# sheet4.net
KiCad netlist of a schematic drawn in Altium Designer
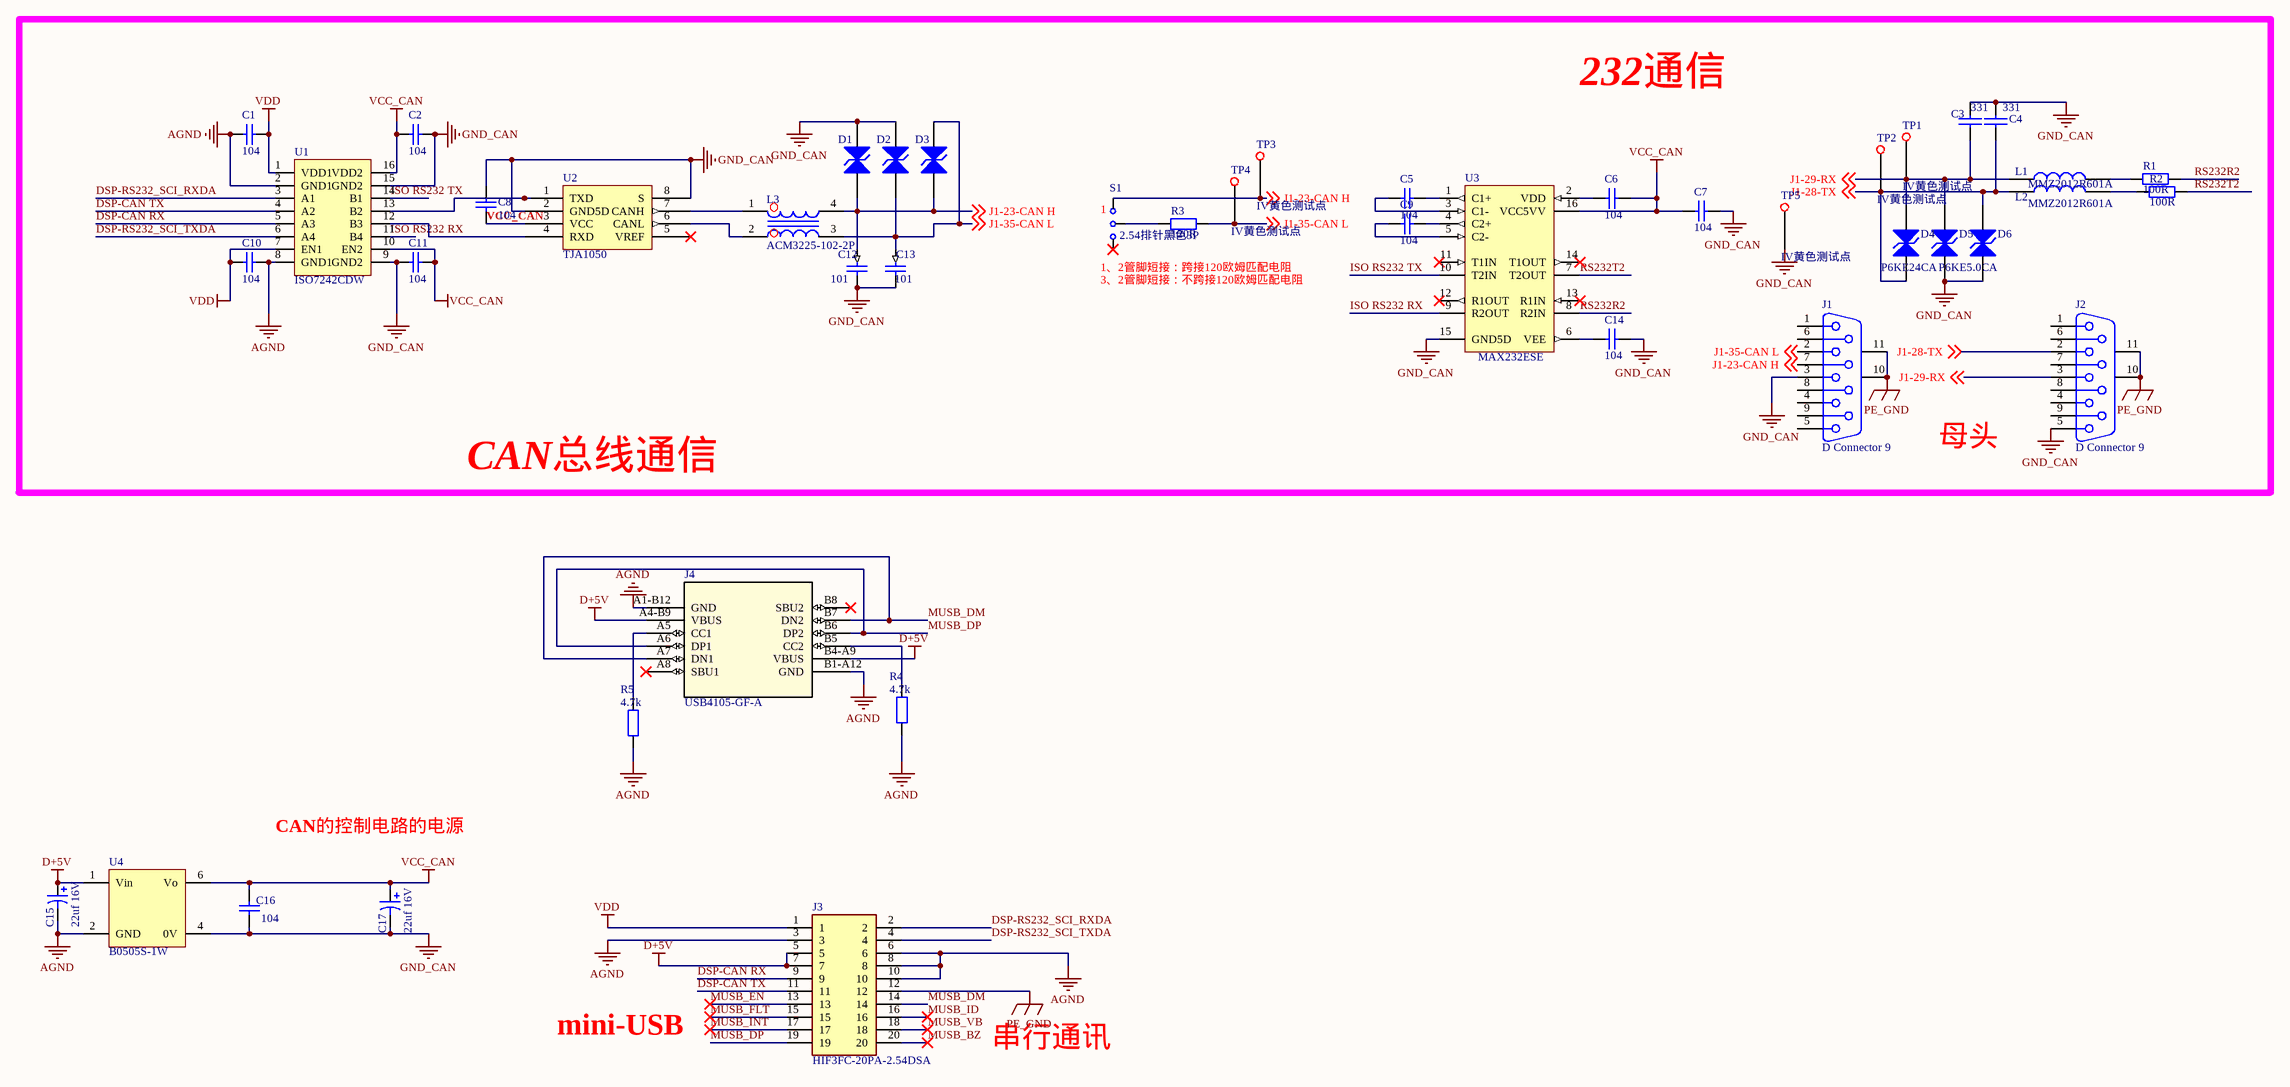
[diagram p0: sheet4.SchDoc]

(export (version "E")
  (design (tool "Eeschema 10.0.6"))
  (components
    (comp (ref "C1")
      (value "104")
      (footprint "0805")
      (description "Capacitor")
      (fields (field (name "PUBLISHER") "Altium Limited"))
      (libsource (lib "Miscellaneous Devices") (part "Cap"))
    )
    (comp (ref "C2")
      (value "104")
      (footprint "0805")
      (description "Capacitor")
      (fields (field (name "PUBLISHER") "Altium Limited"))
      (libsource (lib "Miscellaneous Devices") (part "Cap"))
    )
    (comp (ref "C3") (value "331") (footprint "0805") (libsource (lib "*") (part "2KWC2.S01_100nf_54")))
    (comp (ref "C4") (value "331") (footprint "0805") (libsource (lib "*") (part "2KWC2.S01_100nf_54")))
    (comp (ref "C5")
      (value "104")
      (footprint "0805")
      (description "Capacitor")
      (fields (field (name "PUBLISHER") "Altium Limited"))
      (libsource (lib "Miscellaneous Devices") (part "Cap"))
    )
    (comp (ref "C6")
      (value "104")
      (footprint "0805")
      (description "Capacitor")
      (fields (field (name "PUBLISHER") "Altium Limited"))
      (libsource (lib "Miscellaneous Devices") (part "Cap"))
    )
    (comp (ref "C7")
      (value "104")
      (footprint "0805")
      (description "Capacitor")
      (fields (field (name "PUBLISHER") "Altium Limited"))
      (libsource (lib "Miscellaneous Devices") (part "Cap"))
    )
    (comp (ref "C8")
      (value "104")
      (footprint "0805")
      (description "Capacitor")
      (fields (field (name "PUBLISHER") "Altium Limited"))
      (libsource (lib "Miscellaneous Devices") (part "Cap"))
    )
    (comp (ref "C9")
      (value "104")
      (footprint "0805")
      (description "Capacitor")
      (fields (field (name "PUBLISHER") "Altium Limited"))
      (libsource (lib "Miscellaneous Devices") (part "Cap"))
    )
    (comp (ref "C10")
      (value "104")
      (footprint "0805")
      (description "Capacitor")
      (fields (field (name "PUBLISHER") "Altium Limited"))
      (libsource (lib "Miscellaneous Devices") (part "Cap"))
    )
    (comp (ref "C11")
      (value "104")
      (footprint "0805")
      (description "Capacitor")
      (fields (field (name "PUBLISHER") "Altium Limited"))
      (libsource (lib "Miscellaneous Devices") (part "Cap"))
    )
    (comp (ref "C12")
      (value "101")
      (footprint "0805")
      (description "Capacitor")
      (fields (field (name "PUBLISHER") "Altium Limited"))
      (libsource (lib "*") (part "Cap"))
    )
    (comp (ref "C13")
      (value "101")
      (footprint "0805")
      (description "Capacitor")
      (fields (field (name "PUBLISHER") "Altium Limited"))
      (libsource (lib "*") (part "Cap"))
    )
    (comp (ref "C14")
      (value "104")
      (footprint "0805")
      (description "Capacitor")
      (fields (field (name "PUBLISHER") "Altium Limited"))
      (libsource (lib "Miscellaneous Devices") (part "Cap"))
    )
    (comp (ref "C15")
      (value "22uf 16V")
      (footprint "1206 (钽电容)")
      (description "Polarized Capacitor (Radial)")
      (fields (field (name "PUBLISHER") "Altium Limited"))
      (libsource (lib "*") (part "Cap Pol1"))
    )
    (comp (ref "C16")
      (value "104")
      (footprint "0805")
      (description "Capacitor")
      (fields (field (name "PUBLISHER") "Altium Limited"))
      (libsource (lib "*") (part "Cap"))
    )
    (comp (ref "C17")
      (value "22uf 16V")
      (footprint "1206 (钽电容)")
      (description "Polarized Capacitor (Radial)")
      (fields (field (name "PUBLISHER") "Altium Limited"))
      (libsource (lib "*") (part "Cap Pol1"))
    )
    (comp (ref "D1") (value "~") (footprint "DO214AA") (libsource (lib "Project_Arsene") (part "D ZENER2")))
    (comp (ref "D2") (value "~") (footprint "DO214AA") (libsource (lib "Project_Arsene") (part "D ZENER2")))
    (comp (ref "D3") (value "~") (footprint "DO214AA") (libsource (lib "Project_Arsene") (part "D ZENER2")))
    (comp (ref "D4")
      (value "P6KE24CA")
      (footprint "DO214AA")
      (libsource (lib "Project_Arsene") (part "D ZENER2"))
    )
    (comp (ref "D5")
      (value "P6KE5.0CA")
      (footprint "DO214AA")
      (libsource (lib "Project_Arsene") (part "D ZENER2"))
    )
    (comp (ref "D6") (value "~") (footprint "DO214AA") (libsource (lib "Project_Arsene") (part "D ZENER2")))
    (comp (ref "J1")
      (value "D Connector 9")
      (footprint "DSUB1.385-2H9")
      (description "Receptacle Assembly, 9 Position, Right Angle")
      (fields (field (name "PUBLISHER") "Altium Limited"))
      (libsource (lib "Miscellaneous Connectors") (part "D Connector 9"))
    )
    (comp (ref "J2")
      (value "D Connector 9")
      (footprint "DSUB1.385-2H9")
      (description "Receptacle Assembly, 9 Position, Right Angle")
      (fields (field (name "PUBLISHER") "Altium Limited"))
      (libsource (lib "Miscellaneous Connectors") (part "D Connector 9"))
    )
    (comp (ref "J3")
      (value "HIF3FC-20PA-2.54DSA")
      (footprint "SHDR20W56P254_2X10_3290X850X950P")
      (description "Connector")
      (fields
        (field (name "MANUFACTURER_PART_NUMBER") "HIF3FC-20PA-2.54DSA(71)")
        (field (name "MOUSER PART NUMBER") "798-HIF3FC20PA254D71")
      )
      (libsource (lib "Project_Arsene") (part "HIF3FC-20PA-2.54DSA"))
    )
    (comp (ref "J4")
      (value "USB4105-GF-A")
      (footprint "USB4105_GCT")
      (description "No Description Available")
      (fields (field (name "COPYRIGHT") "Copyright (C) 2022 Ultra Librarian. All rights reserved."))
      (libsource (lib "USB4105-GF-A") (part "USB4105-GF-A"))
    )
    (comp (ref "L1") (value "MMZ2012R601A") (footprint "0805") (libsource (lib "*") (part "INDUCTOR")))
    (comp (ref "L2") (value "MMZ2012R601A") (footprint "0805") (libsource (lib "*") (part "INDUCTOR")))
    (comp (ref "L3") (value "ACM3225-102-2P") (footprint "ACM3225") (libsource (lib "*") (part "T6")))
    (comp (ref "R1")
      (value "100R")
      (footprint "0805")
      (description "Resistor")
      (fields (field (name "PUBLISHER") "Altium Limited"))
      (libsource (lib "") (part "Res2_1"))
    )
    (comp (ref "R2")
      (value "100R")
      (footprint "0805")
      (description "Resistor")
      (fields (field (name "PUBLISHER") "Altium Limited"))
      (libsource (lib "") (part "Res2_1"))
    )
    (comp (ref "R3")
      (value "120R")
      (footprint "0805")
      (description "Resistor")
      (fields (field (name "PUBLISHER") "Altium Limited"))
      (libsource (lib "") (part "Res2_1"))
    )
    (comp (ref "R4")
      (value "4.7k")
      (footprint "0805")
      (description "Resistor")
      (fields (field (name "PUBLISHER") "Altium Limited"))
      (libsource (lib "Miscellaneous Devices") (part "Res2"))
    )
    (comp (ref "R5")
      (value "4.7k")
      (footprint "0805")
      (description "Resistor")
      (fields (field (name "PUBLISHER") "Altium Limited"))
      (libsource (lib "Miscellaneous Devices") (part "Res2"))
    )
    (comp (ref "S1") (value "2.54排针黑色3P") (footprint "SIP3") (libsource (lib "*") (part "SIP3")))
    (comp (ref "TP1") (value "IV黄色测试点") (footprint "TP") (libsource (lib "KING") (part "测试点")))
    (comp (ref "TP2") (value "IV黄色测试点") (footprint "TP") (libsource (lib "KING") (part "测试点")))
    (comp (ref "TP3") (value "IV黄色测试点") (footprint "TP") (libsource (lib "KING") (part "测试点")))
    (comp (ref "TP4") (value "IV黄色测试点") (footprint "TP") (libsource (lib "KING") (part "测试点")))
    (comp (ref "TP5") (value "IV黄色测试点") (footprint "TP") (libsource (lib "KING") (part "测试点")))
    (comp (ref "U1") (value "ISO7242CDW") (footprint "SOIC16_L") (libsource (lib "*") (part "Component_1")))
    (comp (ref "U2")
      (value "TJA1050")
      (footprint "sot96-1_n")
      (description "U?")
      (libsource (lib "*") (part "AT24C02"))
    )
    (comp (ref "U3")
      (value "MAX232ESE")
      (footprint "NSO16_N")
      (description "+5V Powered, Multi-Channel RS-232 Driver/Receiver")
      (fields (field (name "PUBLISHER") "Altium Limited"))
      (libsource (lib "*") (part "MAX232ESE"))
    )
    (comp (ref "U4")
      (value "B0505S-1W")
      (footprint "B0505S-1W")
      (libsource (lib "KING") (part "IB0505LS-W75"))
    )
  )
  (nets
    (net (code "1") (name "/DSP-CAN RX") (class "Default")
      (node (ref "J3") (pin "9") (pinfunction "9_9") (pintype "passive"))
      (node (ref "U1") (pin "5") (pinfunction "A3_5") (pintype "passive"))
    )
    (net (code "2") (name "/DSP-CAN TX") (class "Default")
      (node (ref "J3") (pin "11") (pinfunction "11_11") (pintype "passive"))
      (node (ref "U1") (pin "4") (pinfunction "A2_4") (pintype "passive"))
    )
    (net (code "3") (name "/DSP-RS232_SCI_RXDA") (class "Default")
      (node (ref "J3") (pin "2") (pinfunction "2_2") (pintype "passive"))
      (node (ref "U1") (pin "3") (pinfunction "A1_3") (pintype "passive"))
    )
    (net (code "4") (name "/DSP-RS232_SCI_TXDA") (class "Default")
      (node (ref "J3") (pin "4") (pinfunction "4_4") (pintype "passive"))
      (node (ref "U1") (pin "6") (pinfunction "A4_6") (pintype "passive"))
    )
    (net (code "5") (name "/ISO RS232 RX") (class "Default")
      (node (ref "U1") (pin "11") (pinfunction "B4_11") (pintype "passive"))
      (node (ref "U3") (pin "9") (pinfunction "R2OUT_9") (pintype "passive"))
    )
    (net (code "6") (name "/ISO RS232 TX") (class "Default")
      (node (ref "U1") (pin "14") (pinfunction "B1_14") (pintype "passive"))
      (node (ref "U3") (pin "10") (pinfunction "T2IN_10") (pintype "passive"))
    )
    (net (code "7") (name "/MUSB_BZ") (class "Default")
      (node (ref "J3") (pin "20") (pinfunction "20_20") (pintype "passive+no_connect"))
    )
    (net (code "8") (name "/MUSB_DM") (class "Default")
      (node (ref "J3") (pin "14") (pinfunction "14_14") (pintype "passive"))
      (node (ref "J4") (pin "A7") (pinfunction "DN1_A7") (pintype "bidirectional"))
      (node (ref "J4") (pin "B7") (pinfunction "DN2_B7") (pintype "bidirectional"))
    )
    (net (code "9") (name "/MUSB_DP") (class "Default")
      (node (ref "J3") (pin "19") (pinfunction "19_19") (pintype "passive"))
      (node (ref "J4") (pin "A6") (pinfunction "DP1_A6") (pintype "bidirectional"))
      (node (ref "J4") (pin "B6") (pinfunction "DP2_B6") (pintype "bidirectional"))
    )
    (net (code "10") (name "/MUSB_EN") (class "Default")
      (node (ref "J3") (pin "13") (pinfunction "13_13") (pintype "passive+no_connect"))
    )
    (net (code "11") (name "/MUSB_FLT") (class "Default")
      (node (ref "J3") (pin "15") (pinfunction "15_15") (pintype "passive+no_connect"))
    )
    (net (code "12") (name "/MUSB_ID") (class "Default")
      (node (ref "J3") (pin "16") (pinfunction "16_16") (pintype "passive+no_connect"))
    )
    (net (code "13") (name "/MUSB_INT") (class "Default")
      (node (ref "J3") (pin "17") (pinfunction "17_17") (pintype "passive+no_connect"))
    )
    (net (code "14") (name "/MUSB_VB") (class "Default")
      (node (ref "J3") (pin "18") (pinfunction "18_18") (pintype "passive+no_connect"))
    )
    (net (code "15") (name "/RS232R2") (class "Default")
      (node (ref "R1") (pin "1") (pinfunction "1_1") (pintype "passive"))
      (node (ref "U3") (pin "8") (pinfunction "R2IN_8") (pintype "passive"))
    )
    (net (code "16") (name "/RS232T2") (class "Default")
      (node (ref "R2") (pin "1") (pinfunction "1_1") (pintype "passive"))
      (node (ref "U3") (pin "7") (pinfunction "T2OUT_7") (pintype "passive"))
    )
    (net (code "17") (name "AGND") (class "Default")
      (node (ref "C1") (pin "1") (pinfunction "1_1") (pintype "passive"))
      (node (ref "C10") (pin "2") (pinfunction "2_2") (pintype "passive"))
      (node (ref "C15") (pin "2") (pinfunction "2_2") (pintype "passive"))
      (node (ref "J3") (pin "10") (pinfunction "10_10") (pintype "passive"))
      (node (ref "J3") (pin "3") (pinfunction "3_3") (pintype "passive"))
      (node (ref "J3") (pin "6") (pinfunction "6_6") (pintype "passive"))
      (node (ref "J3") (pin "8") (pinfunction "8_8") (pintype "passive"))
      (node (ref "J4") (pin "A1-B12") (pinfunction "GND_A1-B12") (pintype "passive"))
      (node (ref "J4") (pin "B1-A12") (pinfunction "GND_B1-A12") (pintype "passive"))
      (node (ref "R4") (pin "1") (pinfunction "1_1") (pintype "passive"))
      (node (ref "R5") (pin "1") (pinfunction "1_1") (pintype "passive"))
      (node (ref "U1") (pin "2") (pinfunction "GND1_2") (pintype "passive"))
      (node (ref "U1") (pin "8") (pinfunction "GND1_8") (pintype "passive"))
      (node (ref "U4") (pin "2") (pinfunction "GND_2") (pintype "passive"))
    )
    (net (code "18") (name "D+5V") (class "Default")
      (node (ref "C15") (pin "1") (pinfunction "1_1") (pintype "passive"))
      (node (ref "J3") (pin "5") (pinfunction "5_5") (pintype "passive"))
      (node (ref "J3") (pin "7") (pinfunction "7_7") (pintype "passive"))
      (node (ref "J4") (pin "A4-B9") (pinfunction "VBUS_A4-B9") (pintype "power_in"))
      (node (ref "J4") (pin "B4-A9") (pinfunction "VBUS_B4-A9") (pintype "power_in"))
      (node (ref "U4") (pin "1") (pinfunction "Vin_1") (pintype "passive"))
    )
    (net (code "19") (name "GND_CAN") (class "Default")
      (node (ref "C11") (pin "1") (pinfunction "1_1") (pintype "passive"))
      (node (ref "C12") (pin "1") (pinfunction "1_1") (pintype "passive"))
      (node (ref "C13") (pin "1") (pinfunction "1_1") (pintype "passive"))
      (node (ref "C14") (pin "2") (pinfunction "2_2") (pintype "passive"))
      (node (ref "C16") (pin "1") (pinfunction "1_1") (pintype "passive"))
      (node (ref "C17") (pin "2") (pinfunction "2_2") (pintype "passive"))
      (node (ref "C2") (pin "2") (pinfunction "2_2") (pintype "passive"))
      (node (ref "C3") (pin "1") (pintype "passive"))
      (node (ref "C4") (pin "1") (pintype "passive"))
      (node (ref "C7") (pin "2") (pinfunction "2_2") (pintype "passive"))
      (node (ref "C8") (pin "1") (pinfunction "1_1") (pintype "passive"))
      (node (ref "D1") (pin "2") (pinfunction "K_2") (pintype "passive"))
      (node (ref "D2") (pin "2") (pinfunction "K_2") (pintype "passive"))
      (node (ref "D5") (pin "1") (pinfunction "A_1") (pintype "passive"))
      (node (ref "D6") (pin "1") (pinfunction "A_1") (pintype "passive"))
      (node (ref "J1") (pin "3") (pinfunction "3_3") (pintype "passive"))
      (node (ref "J2") (pin "5") (pinfunction "5_5") (pintype "passive"))
      (node (ref "TP5") (pin "1") (pintype "passive"))
      (node (ref "U1") (pin "15") (pinfunction "GND2_15") (pintype "passive"))
      (node (ref "U1") (pin "9") (pinfunction "GND2_9") (pintype "passive"))
      (node (ref "U2") (pin "2") (pinfunction "GND5D_2") (pintype "passive"))
      (node (ref "U2") (pin "8") (pinfunction "S_8") (pintype "passive"))
      (node (ref "U3") (pin "15") (pinfunction "GND5D_15") (pintype "power_in"))
      (node (ref "U4") (pin "4") (pinfunction "0V_4") (pintype "passive"))
    )
    (net (code "20") (name "J1-23-CAN H") (class "Default")
      (node (ref "C12") (pin "2") (pinfunction "2_2") (pintype "passive"))
      (node (ref "D1") (pin "1") (pinfunction "A_1") (pintype "passive"))
      (node (ref "D3") (pin "1") (pinfunction "A_1") (pintype "passive"))
      (node (ref "J1") (pin "7") (pinfunction "7_7") (pintype "passive"))
      (node (ref "L3") (pin "4") (pinfunction "Sec-_4") (pintype "passive"))
      (node (ref "S1") (pin "1") (pintype "passive"))
      (node (ref "TP3") (pin "1") (pintype "passive"))
    )
    (net (code "21") (name "J1-28-TX") (class "Default")
      (node (ref "C4") (pin "2") (pintype "passive"))
      (node (ref "D4") (pin "1") (pinfunction "A_1") (pintype "passive"))
      (node (ref "D6") (pin "2") (pinfunction "K_2") (pintype "passive"))
      (node (ref "J2") (pin "2") (pinfunction "2_2") (pintype "passive"))
      (node (ref "L2") (pin "1") (pinfunction "1_1") (pintype "passive"))
      (node (ref "TP2") (pin "1") (pintype "passive"))
    )
    (net (code "22") (name "J1-29-RX") (class "Default")
      (node (ref "C3") (pin "2") (pintype "passive"))
      (node (ref "D4") (pin "2") (pinfunction "K_2") (pintype "passive"))
      (node (ref "D5") (pin "2") (pinfunction "K_2") (pintype "passive"))
      (node (ref "J2") (pin "3") (pinfunction "3_3") (pintype "passive"))
      (node (ref "L1") (pin "1") (pinfunction "1_1") (pintype "passive"))
      (node (ref "TP1") (pin "1") (pintype "passive"))
    )
    (net (code "23") (name "J1-35-CAN L") (class "Default")
      (node (ref "C13") (pin "2") (pinfunction "2_2") (pintype "passive"))
      (node (ref "D2") (pin "1") (pinfunction "A_1") (pintype "passive"))
      (node (ref "D3") (pin "2") (pinfunction "K_2") (pintype "passive"))
      (node (ref "J1") (pin "2") (pinfunction "2_2") (pintype "passive"))
      (node (ref "L3") (pin "3") (pinfunction "Pri+_3") (pintype "passive"))
      (node (ref "R3") (pin "1") (pinfunction "1_1") (pintype "passive"))
      (node (ref "TP4") (pin "1") (pintype "passive"))
    )
    (net (code "24") (name "Net-(J4-CC1)") (class "Default")
      (node (ref "J4") (pin "A5") (pinfunction "CC1_A5") (pintype "bidirectional"))
      (node (ref "R5") (pin "2") (pinfunction "2_2") (pintype "passive"))
    )
    (net (code "25") (name "Net-(J4-CC2)") (class "Default")
      (node (ref "J4") (pin "B5") (pinfunction "CC2_B5") (pintype "bidirectional"))
      (node (ref "R4") (pin "2") (pinfunction "2_2") (pintype "passive"))
    )
    (net (code "26") (name "Net-(L1-Pad2)") (class "Default")
      (node (ref "L1") (pin "2") (pinfunction "2_2") (pintype "passive"))
      (node (ref "R1") (pin "2") (pinfunction "2_2") (pintype "passive"))
    )
    (net (code "27") (name "Net-(L2-Pad2)") (class "Default")
      (node (ref "L2") (pin "2") (pinfunction "2_2") (pintype "passive"))
      (node (ref "R2") (pin "2") (pinfunction "2_2") (pintype "passive"))
    )
    (net (code "28") (name "Net-(L3-Pri-)") (class "Default")
      (node (ref "L3") (pin "2") (pinfunction "Pri-_2") (pintype "passive"))
      (node (ref "U2") (pin "6") (pinfunction "CANL_6") (pintype "output"))
    )
    (net (code "29") (name "Net-(R3-Pad2)") (class "Default")
      (node (ref "R3") (pin "2") (pinfunction "2_2") (pintype "passive"))
      (node (ref "S1") (pin "2") (pintype "passive"))
    )
    (net (code "30") (name "Net-(U1-B2)") (class "Default")
      (node (ref "U1") (pin "13") (pinfunction "B2_13") (pintype "passive"))
      (node (ref "U2") (pin "1") (pinfunction "TXD_1") (pintype "passive"))
    )
    (net (code "31") (name "Net-(U1-B3)") (class "Default")
      (node (ref "U1") (pin "12") (pinfunction "B3_12") (pintype "passive"))
      (node (ref "U2") (pin "4") (pinfunction "RXD_4") (pintype "passive"))
    )
    (net (code "32") (name "Net-(U2-CANH)") (class "Default")
      (node (ref "L3") (pin "1") (pinfunction "Pri+_1") (pintype "passive"))
      (node (ref "U2") (pin "7") (pinfunction "CANH_7") (pintype "output"))
    )
    (net (code "33") (name "Net-(U3-C1+)") (class "Default")
      (node (ref "C5") (pin "2") (pinfunction "2_2") (pintype "passive"))
      (node (ref "U3") (pin "1") (pinfunction "C1+_1") (pintype "output"))
    )
    (net (code "34") (name "Net-(U3-C1-)") (class "Default")
      (node (ref "C5") (pin "1") (pinfunction "1_1") (pintype "passive"))
      (node (ref "U3") (pin "3") (pinfunction "C1-_3") (pintype "input"))
    )
    (net (code "35") (name "Net-(U3-C2+)") (class "Default")
      (node (ref "C9") (pin "2") (pinfunction "2_2") (pintype "passive"))
      (node (ref "U3") (pin "4") (pinfunction "C2+_4") (pintype "output"))
    )
    (net (code "36") (name "Net-(U3-C2-)") (class "Default")
      (node (ref "C9") (pin "1") (pinfunction "1_1") (pintype "passive"))
      (node (ref "U3") (pin "5") (pinfunction "C2-_5") (pintype "input"))
    )
    (net (code "37") (name "Net-(U3-VDD)") (class "Default")
      (node (ref "C6") (pin "1") (pinfunction "1_1") (pintype "passive"))
      (node (ref "U3") (pin "2") (pinfunction "VDD_2") (pintype "input"))
    )
    (net (code "38") (name "Net-(U3-VEE)") (class "Default")
      (node (ref "C14") (pin "1") (pinfunction "1_1") (pintype "passive"))
      (node (ref "U3") (pin "6") (pinfunction "VEE_6") (pintype "output"))
    )
    (net (code "39") (name "PE_GND") (class "Default")
      (node (ref "J1") (pin "10") (pinfunction "MH1_10") (pintype "passive"))
      (node (ref "J1") (pin "11") (pinfunction "MH2_11") (pintype "passive"))
      (node (ref "J2") (pin "10") (pinfunction "MH1_10") (pintype "passive"))
      (node (ref "J2") (pin "11") (pinfunction "MH2_11") (pintype "passive"))
      (node (ref "J3") (pin "12") (pinfunction "12_12") (pintype "passive"))
    )
    (net (code "40") (name "VCC_CAN") (class "Default")
      (node (ref "C11") (pin "2") (pinfunction "2_2") (pintype "passive"))
      (node (ref "C16") (pin "2") (pinfunction "2_2") (pintype "passive"))
      (node (ref "C17") (pin "1") (pinfunction "1_1") (pintype "passive"))
      (node (ref "C2") (pin "1") (pinfunction "1_1") (pintype "passive"))
      (node (ref "C6") (pin "2") (pinfunction "2_2") (pintype "passive"))
      (node (ref "C7") (pin "1") (pinfunction "1_1") (pintype "passive"))
      (node (ref "C8") (pin "2") (pinfunction "2_2") (pintype "passive"))
      (node (ref "U1") (pin "10") (pinfunction "EN2_10") (pintype "passive"))
      (node (ref "U1") (pin "16") (pinfunction "VDD2_16") (pintype "passive"))
      (node (ref "U2") (pin "3") (pinfunction "VCC_3") (pintype "power_in"))
      (node (ref "U3") (pin "16") (pinfunction "VCC5VV_16") (pintype "power_in"))
      (node (ref "U4") (pin "6") (pinfunction "Vo_6") (pintype "passive"))
    )
    (net (code "41") (name "VDD") (class "Default")
      (node (ref "C1") (pin "2") (pinfunction "2_2") (pintype "passive"))
      (node (ref "C10") (pin "1") (pinfunction "1_1") (pintype "passive"))
      (node (ref "J3") (pin "1") (pinfunction "1_1") (pintype "passive"))
      (node (ref "U1") (pin "1") (pinfunction "VDD1_1") (pintype "passive"))
      (node (ref "U1") (pin "7") (pinfunction "EN1_7") (pintype "passive"))
    )
    (net (code "42") (name "unconnected-(J1-Pad1)") (class "Default")
      (node (ref "J1") (pin "1") (pinfunction "1_1") (pintype "passive"))
    )
    (net (code "43") (name "unconnected-(J1-Pad4)") (class "Default")
      (node (ref "J1") (pin "4") (pinfunction "4_4") (pintype "passive"))
    )
    (net (code "44") (name "unconnected-(J1-Pad5)") (class "Default")
      (node (ref "J1") (pin "5") (pinfunction "5_5") (pintype "passive"))
    )
    (net (code "45") (name "unconnected-(J1-Pad6)") (class "Default")
      (node (ref "J1") (pin "6") (pinfunction "6_6") (pintype "passive"))
    )
    (net (code "46") (name "unconnected-(J1-Pad8)") (class "Default")
      (node (ref "J1") (pin "8") (pinfunction "8_8") (pintype "passive"))
    )
    (net (code "47") (name "unconnected-(J1-Pad9)") (class "Default")
      (node (ref "J1") (pin "9") (pinfunction "9_9") (pintype "passive"))
    )
    (net (code "48") (name "unconnected-(J2-Pad1)") (class "Default")
      (node (ref "J2") (pin "1") (pinfunction "1_1") (pintype "passive"))
    )
    (net (code "49") (name "unconnected-(J2-Pad4)") (class "Default")
      (node (ref "J2") (pin "4") (pinfunction "4_4") (pintype "passive"))
    )
    (net (code "50") (name "unconnected-(J2-Pad6)") (class "Default")
      (node (ref "J2") (pin "6") (pinfunction "6_6") (pintype "passive"))
    )
    (net (code "51") (name "unconnected-(J2-Pad7)") (class "Default")
      (node (ref "J2") (pin "7") (pinfunction "7_7") (pintype "passive"))
    )
    (net (code "52") (name "unconnected-(J2-Pad8)") (class "Default")
      (node (ref "J2") (pin "8") (pinfunction "8_8") (pintype "passive"))
    )
    (net (code "53") (name "unconnected-(J2-Pad9)") (class "Default")
      (node (ref "J2") (pin "9") (pinfunction "9_9") (pintype "passive"))
    )
    (net (code "54") (name "unconnected-(J4-SBU1-PadA8)") (class "Default")
      (node (ref "J4") (pin "A8") (pinfunction "SBU1_A8") (pintype "bidirectional+no_connect"))
    )
    (net (code "55") (name "unconnected-(J4-SBU2-PadB8)") (class "Default")
      (node (ref "J4") (pin "B8") (pinfunction "SBU2_B8") (pintype "bidirectional+no_connect"))
    )
    (net (code "56") (name "unconnected-(S1-Pad3)") (class "Default")
      (node (ref "S1") (pin "3") (pintype "passive+no_connect"))
    )
    (net (code "57") (name "unconnected-(U2-VREF-Pad5)") (class "Default")
      (node (ref "U2") (pin "5") (pinfunction "VREF_5") (pintype "passive+no_connect"))
    )
    (net (code "58") (name "unconnected-(U3-R1IN-Pad13)") (class "Default")
      (node (ref "U3") (pin "13") (pinfunction "R1IN_13") (pintype "input+no_connect"))
    )
    (net (code "59") (name "unconnected-(U3-R1OUT-Pad12)") (class "Default")
      (node (ref "U3") (pin "12") (pinfunction "R1OUT_12") (pintype "output+no_connect"))
    )
    (net (code "60") (name "unconnected-(U3-T1IN-Pad11)") (class "Default")
      (node (ref "U3") (pin "11") (pinfunction "T1IN_11") (pintype "input+no_connect"))
    )
    (net (code "61") (name "unconnected-(U3-T1OUT-Pad14)") (class "Default")
      (node (ref "U3") (pin "14") (pinfunction "T1OUT_14") (pintype "output+no_connect"))
    )
  )
)
